# GPS_board_sch.net
KiCad netlist of a schematic drawn in EAGLE
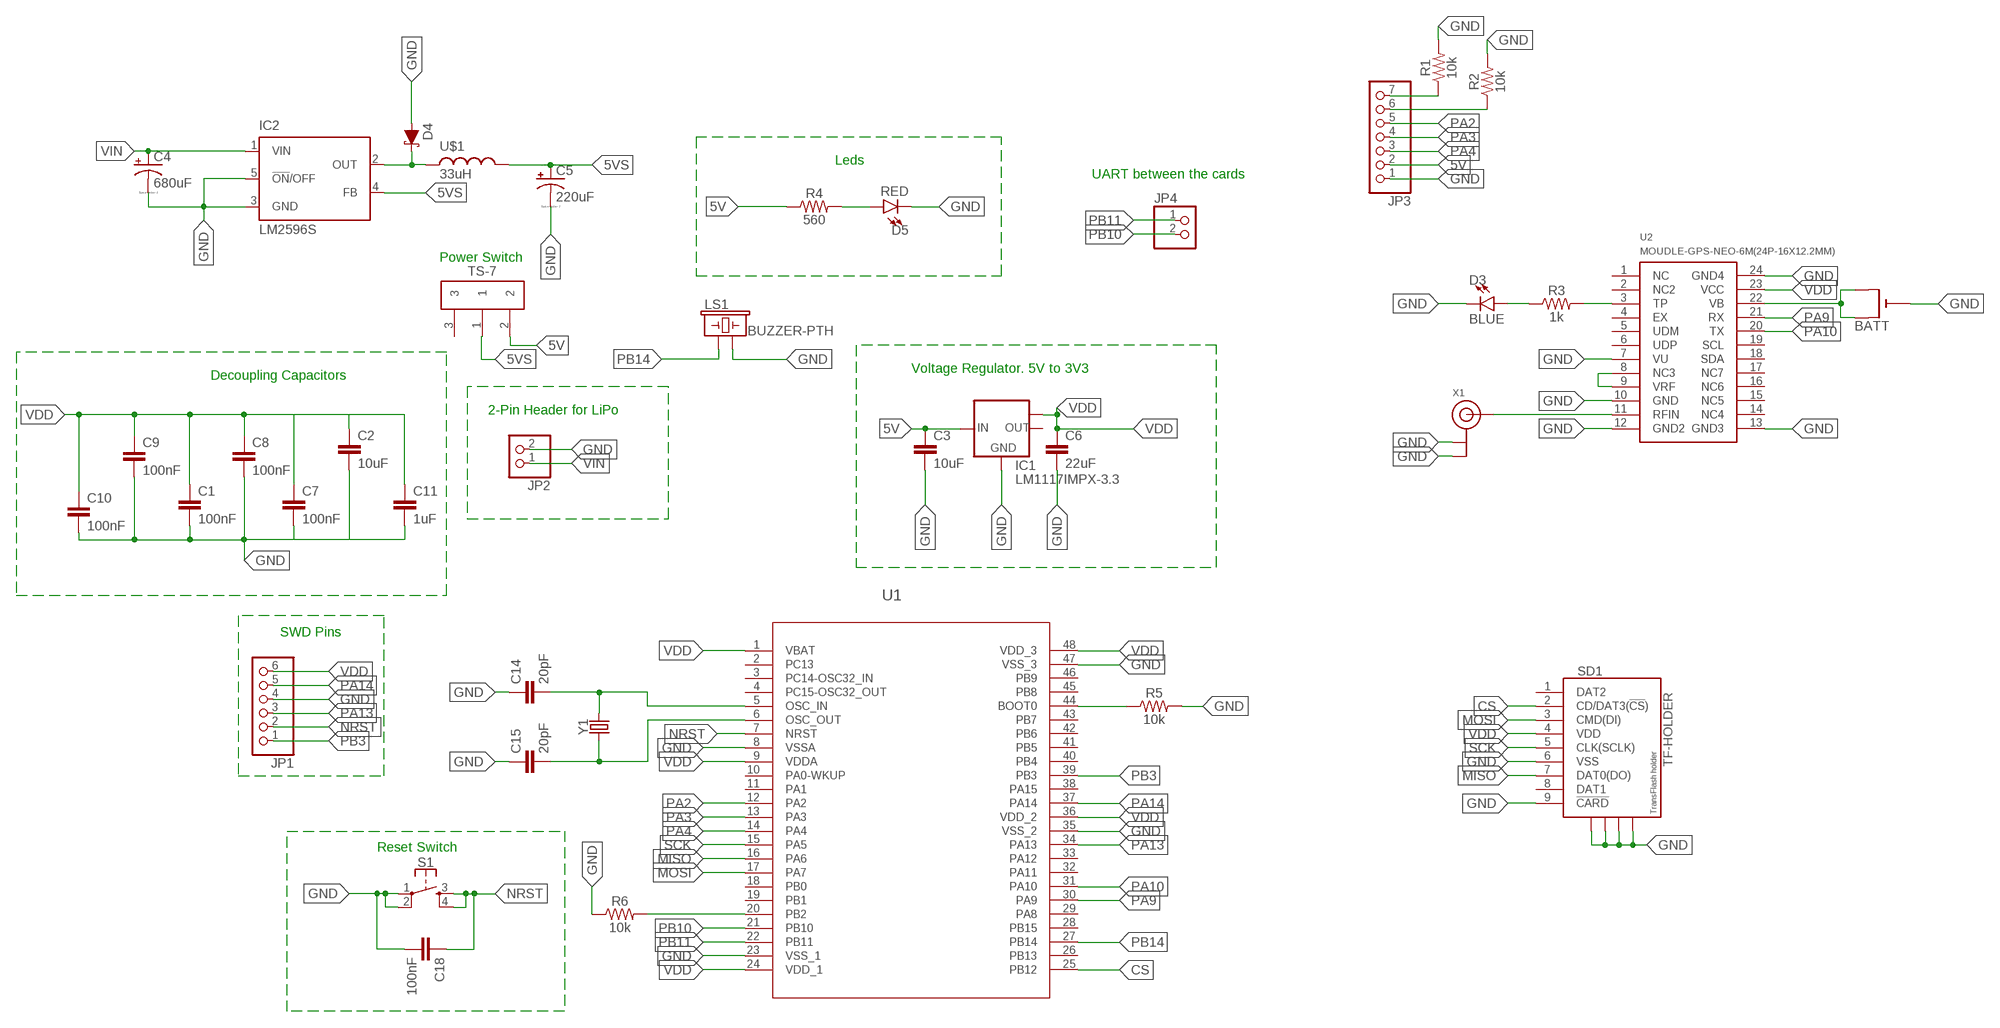
[diagram p0: schematic, sheet 1]

(export (version "E")
  (design (tool "Eeschema 10.0.6"))
  (components
    (comp (ref "BATT")
      (value "CR1220SMT")
      (footprint "eagle-import:CR1220-SMD")
      (libsource (lib "eagle-import") (part "CR1220SMT"))
    )
    (comp (ref "C1")
      (value "100nF")
      (footprint "eagle-import:0805")
      (libsource (lib "eagle-import") (part "10UF-0805-10V-10%"))
    )
    (comp (ref "C2")
      (value "10uF")
      (footprint "eagle-import:0805")
      (libsource (lib "eagle-import") (part "10UF-0805-10V-10%"))
    )
    (comp (ref "C3")
      (value "10uF")
      (footprint "eagle-import:0805")
      (libsource (lib "eagle-import") (part "10UF-0805-10V-10%"))
    )
    (comp (ref "C4")
      (value "680uF")
      (footprint "eagle-import:TT5D7")
      (libsource (lib "eagle-import") (part "CPOL-USTT5D7"))
    )
    (comp (ref "C5")
      (value "220uF")
      (footprint "eagle-import:TT5D7")
      (libsource (lib "eagle-import") (part "CPOL-USTT5D7"))
    )
    (comp (ref "C6")
      (value "22uF")
      (footprint "eagle-import:0805")
      (libsource (lib "eagle-import") (part "10UF-0805-10V-10%"))
    )
    (comp (ref "C7")
      (value "100nF")
      (footprint "eagle-import:0805")
      (libsource (lib "eagle-import") (part "10UF-0805-10V-10%"))
    )
    (comp (ref "C8")
      (value "100nF")
      (footprint "eagle-import:0805")
      (libsource (lib "eagle-import") (part "10UF-0805-10V-10%"))
    )
    (comp (ref "C9")
      (value "100nF")
      (footprint "eagle-import:0805")
      (libsource (lib "eagle-import") (part "10UF-0805-10V-10%"))
    )
    (comp (ref "C10")
      (value "100nF")
      (footprint "eagle-import:0805")
      (libsource (lib "eagle-import") (part "10UF-0805-10V-10%"))
    )
    (comp (ref "C11")
      (value "1uF")
      (footprint "eagle-import:0805")
      (libsource (lib "eagle-import") (part "10UF-0805-10V-10%"))
    )
    (comp (ref "C14")
      (value "20pF")
      (footprint "eagle-import:0805")
      (libsource (lib "eagle-import") (part "10UF-0805-10V-10%"))
    )
    (comp (ref "C15")
      (value "20pF")
      (footprint "eagle-import:0805")
      (libsource (lib "eagle-import") (part "10UF-0805-10V-10%"))
    )
    (comp (ref "C18")
      (value "100nF")
      (footprint "eagle-import:0805")
      (libsource (lib "eagle-import") (part "10UF-0805-10V-10%"))
    )
    (comp (ref "D3")
      (value "BLUE")
      (footprint "eagle-import:LED-1206")
      (libsource (lib "eagle-import") (part "LED-BLUE1206"))
    )
    (comp (ref "D4")
      (value "3A/40V/500mV")
      (footprint "eagle-import:SMA-DIODE")
      (libsource (lib "eagle-import") (part "DIODE-SCHOTTKY-B340A"))
    )
    (comp (ref "D5")
      (value "RED")
      (footprint "eagle-import:LED-1206")
      (libsource (lib "eagle-import") (part "LED-RED1206"))
    )
    (comp (ref "IC1")
      (value "LM1117IMPX-3.3")
      (footprint "eagle-import:SOT223")
      (libsource (lib "eagle-import") (part "LM1117IMPX-3.3"))
    )
    (comp (ref "IC2")
      (value "LM2596S")
      (footprint "eagle-import:TO263-5")
      (fields (field (name "MF") "NATIONAL SEMICONDUCTOR") (field (name "MPN") "LM2596S-ADJ/NOPB"))
      (libsource (lib "eagle-import") (part "LM2596S"))
    )
    (comp (ref "JP1")
      (value "PINHD-1X6")
      (footprint "eagle-import:1X06")
      (libsource (lib "eagle-import") (part "PINHD-1X6"))
    )
    (comp (ref "JP2")
      (value "PINHD-1X2")
      (footprint "eagle-import:1X02")
      (libsource (lib "eagle-import") (part "PINHD-1X2"))
    )
    (comp (ref "JP3")
      (value "PINHD-1X7")
      (footprint "eagle-import:1X07")
      (libsource (lib "eagle-import") (part "PINHD-1X7"))
    )
    (comp (ref "JP4")
      (value "PINHD-1X2/90")
      (footprint "eagle-import:1X02_90")
      (libsource (lib "eagle-import") (part "pinhead_325_PINHD-1X2/90"))
    )
    (comp (ref "LS1")
      (value "BUZZER-PTH")
      (footprint "eagle-import:BUZZER-12MM")
      (libsource (lib "eagle-import") (part "BUZZER-PTH"))
    )
    (comp (ref "R1")
      (value "10k")
      (footprint "eagle-import:0805")
      (libsource (lib "eagle-import") (part "0.3OHM-0805-1/8W-1%"))
    )
    (comp (ref "R2")
      (value "10k")
      (footprint "eagle-import:0805")
      (libsource (lib "eagle-import") (part "0.3OHM-0805-1/8W-1%"))
    )
    (comp (ref "R3")
      (value "1k")
      (footprint "eagle-import:0805")
      (libsource (lib "eagle-import") (part "0.3OHM-0805-1/8W-1%"))
    )
    (comp (ref "R4")
      (value "560")
      (footprint "eagle-import:0805")
      (libsource (lib "eagle-import") (part "0.3OHM-0805-1/8W-1%"))
    )
    (comp (ref "R5")
      (value "10k")
      (footprint "eagle-import:0805")
      (libsource (lib "eagle-import") (part "0.3OHM-0805-1/8W-1%"))
    )
    (comp (ref "R6")
      (value "10k")
      (footprint "eagle-import:0805")
      (libsource (lib "eagle-import") (part "0.3OHM-0805-1/8W-1%"))
    )
    (comp (ref "S1")
      (value "MOMENTARY-SWITCH-SPST-2-SMD-5.2MM")
      (footprint "eagle-import:TACTILE_SWITCH_SMD_5.2MM")
      (libsource (lib "eagle-import") (part "MOMENTARY-SWITCH-SPST-2-SMD-5.2MM"))
    )
    (comp (ref "SD1")
      (value "TF-HOLDER")
      (footprint "eagle-import:TF-PULL")
      (libsource (lib "eagle-import") (part "TF-HOLDER"))
    )
    (comp (ref "TS-7")
      (value "TS-7")
      (footprint "eagle-import:TS7")
      (libsource (lib "eagle-import") (part "TS-7"))
    )
    (comp (ref "U$1")
      (value "33uH")
      (footprint "eagle-import:MSS1260")
      (libsource (lib "eagle-import") (part "MSS1260"))
    )
    (comp (ref "U1")
      (value "STM32F103CXT2")
      (footprint "eagle-import:LQFP48-7X7MM")
      (fields (field (name "MANUFACTURER_PART_NUMBER") "stm32f103cxt2"))
      (libsource (lib "eagle-import") (part "STM32F103CXT2"))
    )
    (comp (ref "U2")
      (value "MOUDLE-GPS-NEO-6M(24P-16X12.2MM)")
      (footprint "eagle-import:GPS24P-SMD-1.1-16X12.2MM")
      (fields (field (name "MF") "u-blox") (field (name "MP") "NEO-6M-GPS"))
      (libsource (lib "eagle-import") (part "MOUDLE-GPS-NEO-6M(24P-16X12.2MM)"))
    )
    (comp (ref "X1")
      (value "ANTENNA_U.FL")
      (footprint "eagle-import:U.FL")
      (libsource (lib "eagle-import") (part "ANTENNA_U.FL"))
    )
    (comp (ref "Y1")
      (value "CRYSTALPTH-HC49US")
      (footprint "eagle-import:HC49US")
      (libsource (lib "eagle-import") (part "CRYSTALPTH-HC49US"))
    )
  )
  (nets
    (net (code "1") (name "5V") (class "Default")
      (node (ref "C3") (pin "1") (pinfunction "1_1") (pintype "passive"))
      (node (ref "IC1") (pin "3") (pinfunction "IN_3") (pintype "input"))
      (node (ref "JP3") (pin "2") (pinfunction "2_2") (pintype "passive"))
      (node (ref "R4") (pin "1") (pinfunction "1_1") (pintype "passive"))
      (node (ref "TS-7") (pin "2") (pinfunction "2_2") (pintype "bidirectional"))
    )
    (net (code "2") (name "5VS") (class "Default")
      (node (ref "C5") (pin "+") (pinfunction "+_+") (pintype "passive"))
      (node (ref "IC2") (pin "4") (pinfunction "FB_4") (pintype "input"))
      (node (ref "TS-7") (pin "1") (pinfunction "1_1") (pintype "bidirectional"))
      (node (ref "U$1") (pin "P$1") (pinfunction "P$1_P$1") (pintype "passive"))
    )
    (net (code "3") (name "CS") (class "Default")
      (node (ref "SD1") (pin "2") (pinfunction "CD/DAT3(~{CS})_2") (pintype "bidirectional"))
      (node (ref "U1") (pin "25") (pinfunction "PB12_25") (pintype "bidirectional"))
    )
    (net (code "4") (name "GND") (class "Default")
      (node (ref "BATT") (pin "-") (pinfunction "-_-") (pintype "passive"))
      (node (ref "C1") (pin "2") (pinfunction "2_2") (pintype "passive"))
      (node (ref "C10") (pin "2") (pinfunction "2_2") (pintype "passive"))
      (node (ref "C11") (pin "2") (pinfunction "2_2") (pintype "passive"))
      (node (ref "C14") (pin "1") (pinfunction "1_1") (pintype "passive"))
      (node (ref "C15") (pin "1") (pinfunction "1_1") (pintype "passive"))
      (node (ref "C18") (pin "2") (pinfunction "2_2") (pintype "passive"))
      (node (ref "C2") (pin "2") (pinfunction "2_2") (pintype "passive"))
      (node (ref "C3") (pin "2") (pinfunction "2_2") (pintype "passive"))
      (node (ref "C4") (pin "-") (pinfunction "-_-") (pintype "passive"))
      (node (ref "C5") (pin "-") (pinfunction "-_-") (pintype "passive"))
      (node (ref "C6") (pin "2") (pinfunction "2_2") (pintype "passive"))
      (node (ref "C7") (pin "2") (pinfunction "2_2") (pintype "passive"))
      (node (ref "C8") (pin "2") (pinfunction "2_2") (pintype "passive"))
      (node (ref "C9") (pin "2") (pinfunction "2_2") (pintype "passive"))
      (node (ref "D3") (pin "C") (pinfunction "C_C") (pintype "passive"))
      (node (ref "D4") (pin "A") (pinfunction "A_A") (pintype "passive"))
      (node (ref "D5") (pin "C") (pinfunction "C_C") (pintype "passive"))
      (node (ref "IC1") (pin "1") (pinfunction "GND_1") (pintype "input"))
      (node (ref "IC2") (pin "3") (pinfunction "GND_3") (pintype "power_in"))
      (node (ref "IC2") (pin "5") (pinfunction "~{ON}/OFF_5") (pintype "input"))
      (node (ref "JP1") (pin "4") (pinfunction "4_4") (pintype "passive"))
      (node (ref "JP2") (pin "2") (pinfunction "2_2") (pintype "passive"))
      (node (ref "JP3") (pin "1") (pinfunction "1_1") (pintype "passive"))
      (node (ref "LS1") (pin "-") (pinfunction "2_-") (pintype "passive"))
      (node (ref "R1") (pin "2") (pinfunction "2_2") (pintype "passive"))
      (node (ref "R2") (pin "2") (pinfunction "2_2") (pintype "passive"))
      (node (ref "R5") (pin "2") (pinfunction "2_2") (pintype "passive"))
      (node (ref "R6") (pin "1") (pinfunction "1_1") (pintype "passive"))
      (node (ref "S1") (pin "1") (pinfunction "1_1") (pintype "passive"))
      (node (ref "S1") (pin "2") (pinfunction "2_2") (pintype "passive"))
      (node (ref "SD1") (pin "6") (pinfunction "VSS_6") (pintype "power_in"))
      (node (ref "SD1") (pin "9") (pinfunction "~{CARD}_9") (pintype "passive"))
      (node (ref "SD1") (pin "S1") (pinfunction "S1_S1") (pintype "passive"))
      (node (ref "SD1") (pin "S2") (pinfunction "S2_S2") (pintype "passive"))
      (node (ref "SD1") (pin "S3") (pinfunction "S3_S3") (pintype "passive"))
      (node (ref "SD1") (pin "S4") (pinfunction "S4_S4") (pintype "passive"))
      (node (ref "U1") (pin "23") (pinfunction "VSS_1_23") (pintype "power_in"))
      (node (ref "U1") (pin "35") (pinfunction "VSS_2_35") (pintype "power_in"))
      (node (ref "U1") (pin "47") (pinfunction "VSS_3_47") (pintype "power_in"))
      (node (ref "U1") (pin "8") (pinfunction "VSSA_8") (pintype "power_in"))
      (node (ref "U2") (pin "10") (pinfunction "GND_10") (pintype "bidirectional"))
      (node (ref "U2") (pin "12") (pinfunction "GND2_12") (pintype "bidirectional"))
      (node (ref "U2") (pin "13") (pinfunction "GND3_13") (pintype "bidirectional"))
      (node (ref "U2") (pin "24") (pinfunction "GND4_24") (pintype "bidirectional"))
      (node (ref "U2") (pin "7") (pinfunction "VU_7") (pintype "bidirectional"))
      (node (ref "X1") (pin "1") (pinfunction "GND_1") (pintype "passive"))
      (node (ref "X1") (pin "2") (pinfunction "GND_2") (pintype "passive"))
    )
    (net (code "5") (name "MISO") (class "Default")
      (node (ref "SD1") (pin "7") (pinfunction "DAT0(DO)_7") (pintype "bidirectional"))
      (node (ref "U1") (pin "16") (pinfunction "PA6_16") (pintype "bidirectional"))
    )
    (net (code "6") (name "MOSI") (class "Default")
      (node (ref "SD1") (pin "3") (pinfunction "CMD(DI)_3") (pintype "bidirectional"))
      (node (ref "U1") (pin "17") (pinfunction "PA7_17") (pintype "bidirectional"))
    )
    (net (code "7") (name "NRST") (class "Default")
      (node (ref "C18") (pin "1") (pinfunction "1_1") (pintype "passive"))
      (node (ref "JP1") (pin "2") (pinfunction "2_2") (pintype "passive"))
      (node (ref "S1") (pin "3") (pinfunction "3_3") (pintype "passive"))
      (node (ref "S1") (pin "4") (pinfunction "4_4") (pintype "passive"))
      (node (ref "U1") (pin "7") (pinfunction "NRST_7") (pintype "bidirectional"))
    )
    (net (code "8") (name "Net-(BATT-+)") (class "Default")
      (node (ref "BATT") (pin "+$1") (pinfunction "+_+$1") (pintype "passive"))
      (node (ref "BATT") (pin "+$2") (pinfunction "+1_+$2") (pintype "passive"))
      (node (ref "U2") (pin "22") (pinfunction "VB_22") (pintype "bidirectional"))
    )
    (net (code "9") (name "Net-(D3-PadA)") (class "Default")
      (node (ref "D3") (pin "A") (pinfunction "A_A") (pintype "passive"))
      (node (ref "R3") (pin "1") (pinfunction "1_1") (pintype "passive"))
    )
    (net (code "10") (name "Net-(D5-PadA)") (class "Default")
      (node (ref "D5") (pin "A") (pinfunction "A_A") (pintype "passive"))
      (node (ref "R4") (pin "2") (pinfunction "2_2") (pintype "passive"))
    )
    (net (code "11") (name "Net-(IC2-OUT)") (class "Default")
      (node (ref "D4") (pin "C") (pinfunction "C_C") (pintype "passive"))
      (node (ref "IC2") (pin "2") (pinfunction "OUT_2") (pintype "output"))
      (node (ref "U$1") (pin "P$2") (pinfunction "P$2_P$2") (pintype "passive"))
    )
    (net (code "12") (name "Net-(JP3-Pad6)") (class "Default")
      (node (ref "JP3") (pin "6") (pinfunction "6_6") (pintype "passive"))
      (node (ref "R2") (pin "1") (pinfunction "1_1") (pintype "passive"))
    )
    (net (code "13") (name "Net-(JP3-Pad7)") (class "Default")
      (node (ref "JP3") (pin "7") (pinfunction "7_7") (pintype "passive"))
      (node (ref "R1") (pin "1") (pinfunction "1_1") (pintype "passive"))
    )
    (net (code "14") (name "Net-(U1-BOOT0)") (class "Default")
      (node (ref "R5") (pin "1") (pinfunction "1_1") (pintype "passive"))
      (node (ref "U1") (pin "44") (pinfunction "BOOT0_44") (pintype "input"))
    )
    (net (code "15") (name "Net-(U1-OSC_IN)") (class "Default")
      (node (ref "C14") (pin "2") (pinfunction "2_2") (pintype "passive"))
      (node (ref "U1") (pin "5") (pinfunction "OSC_IN_5") (pintype "input"))
      (node (ref "Y1") (pin "2") (pinfunction "2_2") (pintype "passive"))
    )
    (net (code "16") (name "Net-(U1-OSC_OUT)") (class "Default")
      (node (ref "C15") (pin "2") (pinfunction "2_2") (pintype "passive"))
      (node (ref "U1") (pin "6") (pinfunction "OSC_OUT_6") (pintype "output"))
      (node (ref "Y1") (pin "1") (pinfunction "1_1") (pintype "passive"))
    )
    (net (code "17") (name "Net-(U1-PB2)") (class "Default")
      (node (ref "R6") (pin "2") (pinfunction "2_2") (pintype "passive"))
      (node (ref "U1") (pin "20") (pinfunction "PB2_20") (pintype "bidirectional"))
    )
    (net (code "18") (name "Net-(U2-NC3)") (class "Default")
      (node (ref "U2") (pin "8") (pinfunction "NC3_8") (pintype "bidirectional"))
      (node (ref "U2") (pin "9") (pinfunction "VRF_9") (pintype "bidirectional"))
    )
    (net (code "19") (name "Net-(U2-RFIN)") (class "Default")
      (node (ref "U2") (pin "11") (pinfunction "RFIN_11") (pintype "bidirectional"))
      (node (ref "X1") (pin "3") (pinfunction "SIGNAL_3") (pintype "passive"))
    )
    (net (code "20") (name "Net-(U2-TP)") (class "Default")
      (node (ref "R3") (pin "2") (pinfunction "2_2") (pintype "passive"))
      (node (ref "U2") (pin "3") (pinfunction "TP_3") (pintype "bidirectional"))
    )
    (net (code "21") (name "PA2") (class "Default")
      (node (ref "JP3") (pin "5") (pinfunction "5_5") (pintype "passive"))
      (node (ref "U1") (pin "12") (pinfunction "PA2_12") (pintype "bidirectional"))
    )
    (net (code "22") (name "PA3") (class "Default")
      (node (ref "JP3") (pin "4") (pinfunction "4_4") (pintype "passive"))
      (node (ref "U1") (pin "13") (pinfunction "PA3_13") (pintype "bidirectional"))
    )
    (net (code "23") (name "PA4") (class "Default")
      (node (ref "JP3") (pin "3") (pinfunction "3_3") (pintype "passive"))
      (node (ref "U1") (pin "14") (pinfunction "PA4_14") (pintype "bidirectional"))
    )
    (net (code "24") (name "PA9") (class "Default")
      (node (ref "U1") (pin "30") (pinfunction "PA9_30") (pintype "bidirectional"))
      (node (ref "U2") (pin "21") (pinfunction "RX_21") (pintype "bidirectional"))
    )
    (net (code "25") (name "PA10") (class "Default")
      (node (ref "U1") (pin "31") (pinfunction "PA10_31") (pintype "bidirectional"))
      (node (ref "U2") (pin "20") (pinfunction "TX_20") (pintype "bidirectional"))
    )
    (net (code "26") (name "PA13") (class "Default")
      (node (ref "JP1") (pin "3") (pinfunction "3_3") (pintype "passive"))
      (node (ref "U1") (pin "34") (pinfunction "PA13_34") (pintype "bidirectional"))
    )
    (net (code "27") (name "PA14") (class "Default")
      (node (ref "JP1") (pin "5") (pinfunction "5_5") (pintype "passive"))
      (node (ref "U1") (pin "37") (pinfunction "PA14_37") (pintype "bidirectional"))
    )
    (net (code "28") (name "PB3") (class "Default")
      (node (ref "JP1") (pin "1") (pinfunction "1_1") (pintype "passive"))
      (node (ref "U1") (pin "39") (pinfunction "PB3_39") (pintype "bidirectional"))
    )
    (net (code "29") (name "PB10") (class "Default")
      (node (ref "JP4") (pin "2") (pinfunction "2_2") (pintype "passive"))
      (node (ref "U1") (pin "21") (pinfunction "PB10_21") (pintype "bidirectional"))
    )
    (net (code "30") (name "PB11") (class "Default")
      (node (ref "JP4") (pin "1") (pinfunction "1_1") (pintype "passive"))
      (node (ref "U1") (pin "22") (pinfunction "PB11_22") (pintype "bidirectional"))
    )
    (net (code "31") (name "PB14") (class "Default")
      (node (ref "LS1") (pin "+") (pinfunction "1_+") (pintype "passive"))
      (node (ref "U1") (pin "27") (pinfunction "PB14_27") (pintype "bidirectional"))
    )
    (net (code "32") (name "SCK") (class "Default")
      (node (ref "SD1") (pin "5") (pinfunction "CLK(SCLK)_5") (pintype "input"))
      (node (ref "U1") (pin "15") (pinfunction "PA5_15") (pintype "bidirectional"))
    )
    (net (code "33") (name "VDD") (class "Default")
      (node (ref "C1") (pin "1") (pinfunction "1_1") (pintype "passive"))
      (node (ref "C10") (pin "1") (pinfunction "1_1") (pintype "passive"))
      (node (ref "C11") (pin "1") (pinfunction "1_1") (pintype "passive"))
      (node (ref "C2") (pin "1") (pinfunction "1_1") (pintype "passive"))
      (node (ref "C6") (pin "1") (pinfunction "1_1") (pintype "passive"))
      (node (ref "C7") (pin "1") (pinfunction "1_1") (pintype "passive"))
      (node (ref "C8") (pin "1") (pinfunction "1_1") (pintype "passive"))
      (node (ref "C9") (pin "1") (pinfunction "1_1") (pintype "passive"))
      (node (ref "IC1") (pin "TAB") (pinfunction "OUT1_TAB") (pintype "passive"))
      (node (ref "JP1") (pin "6") (pinfunction "6_6") (pintype "passive"))
      (node (ref "SD1") (pin "4") (pinfunction "VDD_4") (pintype "power_in"))
      (node (ref "U1") (pin "1") (pinfunction "VBAT_1") (pintype "power_in"))
      (node (ref "U1") (pin "24") (pinfunction "VDD_1_24") (pintype "power_in"))
      (node (ref "U1") (pin "36") (pinfunction "VDD_2_36") (pintype "power_in"))
      (node (ref "U1") (pin "48") (pinfunction "VDD_3_48") (pintype "power_in"))
      (node (ref "U1") (pin "9") (pinfunction "VDDA_9") (pintype "power_in"))
      (node (ref "U2") (pin "23") (pinfunction "VCC_23") (pintype "bidirectional"))
    )
    (net (code "34") (name "VIN") (class "Default")
      (node (ref "C4") (pin "+") (pinfunction "+_+") (pintype "passive"))
      (node (ref "IC2") (pin "1") (pinfunction "VIN_1") (pintype "input"))
      (node (ref "JP2") (pin "1") (pinfunction "1_1") (pintype "passive"))
    )
    (net (code "35") (name "unconnected-(IC1-OUT-Pad2)") (class "Default")
      (node (ref "IC1") (pin "2") (pinfunction "OUT_2") (pintype "passive"))
    )
    (net (code "36") (name "unconnected-(SD1-DAT1-Pad8)") (class "Default")
      (node (ref "SD1") (pin "8") (pinfunction "DAT1_8") (pintype "bidirectional"))
    )
    (net (code "37") (name "unconnected-(SD1-DAT2-Pad1)") (class "Default")
      (node (ref "SD1") (pin "1") (pinfunction "DAT2_1") (pintype "bidirectional"))
    )
    (net (code "38") (name "unconnected-(TS-7-Pad3)") (class "Default")
      (node (ref "TS-7") (pin "3") (pinfunction "3_3") (pintype "bidirectional"))
    )
    (net (code "39") (name "unconnected-(U1-PA0-WKUP-Pad10)") (class "Default")
      (node (ref "U1") (pin "10") (pinfunction "PA0-WKUP_10") (pintype "bidirectional"))
    )
    (net (code "40") (name "unconnected-(U1-PA1-Pad11)") (class "Default")
      (node (ref "U1") (pin "11") (pinfunction "PA1_11") (pintype "bidirectional"))
    )
    (net (code "41") (name "unconnected-(U1-PA8-Pad29)") (class "Default")
      (node (ref "U1") (pin "29") (pinfunction "PA8_29") (pintype "bidirectional"))
    )
    (net (code "42") (name "unconnected-(U1-PA11-Pad32)") (class "Default")
      (node (ref "U1") (pin "32") (pinfunction "PA11_32") (pintype "bidirectional"))
    )
    (net (code "43") (name "unconnected-(U1-PA12-Pad33)") (class "Default")
      (node (ref "U1") (pin "33") (pinfunction "PA12_33") (pintype "bidirectional"))
    )
    (net (code "44") (name "unconnected-(U1-PA15-Pad38)") (class "Default")
      (node (ref "U1") (pin "38") (pinfunction "PA15_38") (pintype "bidirectional"))
    )
    (net (code "45") (name "unconnected-(U1-PB0-Pad18)") (class "Default")
      (node (ref "U1") (pin "18") (pinfunction "PB0_18") (pintype "bidirectional"))
    )
    (net (code "46") (name "unconnected-(U1-PB1-Pad19)") (class "Default")
      (node (ref "U1") (pin "19") (pinfunction "PB1_19") (pintype "bidirectional"))
    )
    (net (code "47") (name "unconnected-(U1-PB4-Pad40)") (class "Default")
      (node (ref "U1") (pin "40") (pinfunction "PB4_40") (pintype "bidirectional"))
    )
    (net (code "48") (name "unconnected-(U1-PB5-Pad41)") (class "Default")
      (node (ref "U1") (pin "41") (pinfunction "PB5_41") (pintype "bidirectional"))
    )
    (net (code "49") (name "unconnected-(U1-PB6-Pad42)") (class "Default")
      (node (ref "U1") (pin "42") (pinfunction "PB6_42") (pintype "bidirectional"))
    )
    (net (code "50") (name "unconnected-(U1-PB7-Pad43)") (class "Default")
      (node (ref "U1") (pin "43") (pinfunction "PB7_43") (pintype "bidirectional"))
    )
    (net (code "51") (name "unconnected-(U1-PB8-Pad45)") (class "Default")
      (node (ref "U1") (pin "45") (pinfunction "PB8_45") (pintype "bidirectional"))
    )
    (net (code "52") (name "unconnected-(U1-PB9-Pad46)") (class "Default")
      (node (ref "U1") (pin "46") (pinfunction "PB9_46") (pintype "bidirectional"))
    )
    (net (code "53") (name "unconnected-(U1-PB13-Pad26)") (class "Default")
      (node (ref "U1") (pin "26") (pinfunction "PB13_26") (pintype "bidirectional"))
    )
    (net (code "54") (name "unconnected-(U1-PB15-Pad28)") (class "Default")
      (node (ref "U1") (pin "28") (pinfunction "PB15_28") (pintype "bidirectional"))
    )
    (net (code "55") (name "unconnected-(U1-PC13-Pad2)") (class "Default")
      (node (ref "U1") (pin "2") (pinfunction "PC13_2") (pintype "bidirectional"))
    )
    (net (code "56") (name "unconnected-(U1-PC14-OSC32_IN-Pad3)") (class "Default")
      (node (ref "U1") (pin "3") (pinfunction "PC14-OSC32_IN_3") (pintype "bidirectional"))
    )
    (net (code "57") (name "unconnected-(U1-PC15-OSC32_OUT-Pad4)") (class "Default")
      (node (ref "U1") (pin "4") (pinfunction "PC15-OSC32_OUT_4") (pintype "bidirectional"))
    )
    (net (code "58") (name "unconnected-(U2-EX-Pad4)") (class "Default")
      (node (ref "U2") (pin "4") (pinfunction "EX_4") (pintype "bidirectional"))
    )
    (net (code "59") (name "unconnected-(U2-NC-Pad1)") (class "Default")
      (node (ref "U2") (pin "1") (pinfunction "NC_1") (pintype "bidirectional"))
    )
    (net (code "60") (name "unconnected-(U2-NC2-Pad2)") (class "Default")
      (node (ref "U2") (pin "2") (pinfunction "NC2_2") (pintype "bidirectional"))
    )
    (net (code "61") (name "unconnected-(U2-NC4-Pad14)") (class "Default")
      (node (ref "U2") (pin "14") (pinfunction "NC4_14") (pintype "bidirectional"))
    )
    (net (code "62") (name "unconnected-(U2-NC5-Pad15)") (class "Default")
      (node (ref "U2") (pin "15") (pinfunction "NC5_15") (pintype "bidirectional"))
    )
    (net (code "63") (name "unconnected-(U2-NC6-Pad16)") (class "Default")
      (node (ref "U2") (pin "16") (pinfunction "NC6_16") (pintype "bidirectional"))
    )
    (net (code "64") (name "unconnected-(U2-NC7-Pad17)") (class "Default")
      (node (ref "U2") (pin "17") (pinfunction "NC7_17") (pintype "bidirectional"))
    )
    (net (code "65") (name "unconnected-(U2-SCL-Pad19)") (class "Default")
      (node (ref "U2") (pin "19") (pinfunction "SCL_19") (pintype "bidirectional"))
    )
    (net (code "66") (name "unconnected-(U2-SDA-Pad18)") (class "Default")
      (node (ref "U2") (pin "18") (pinfunction "SDA_18") (pintype "bidirectional"))
    )
    (net (code "67") (name "unconnected-(U2-UDM-Pad5)") (class "Default")
      (node (ref "U2") (pin "5") (pinfunction "UDM_5") (pintype "bidirectional"))
    )
    (net (code "68") (name "unconnected-(U2-UDP-Pad6)") (class "Default")
      (node (ref "U2") (pin "6") (pinfunction "UDP_6") (pintype "bidirectional"))
    )
  )
)
